# tia1.net
KiCad netlist of a schematic drawn in Altium Designer
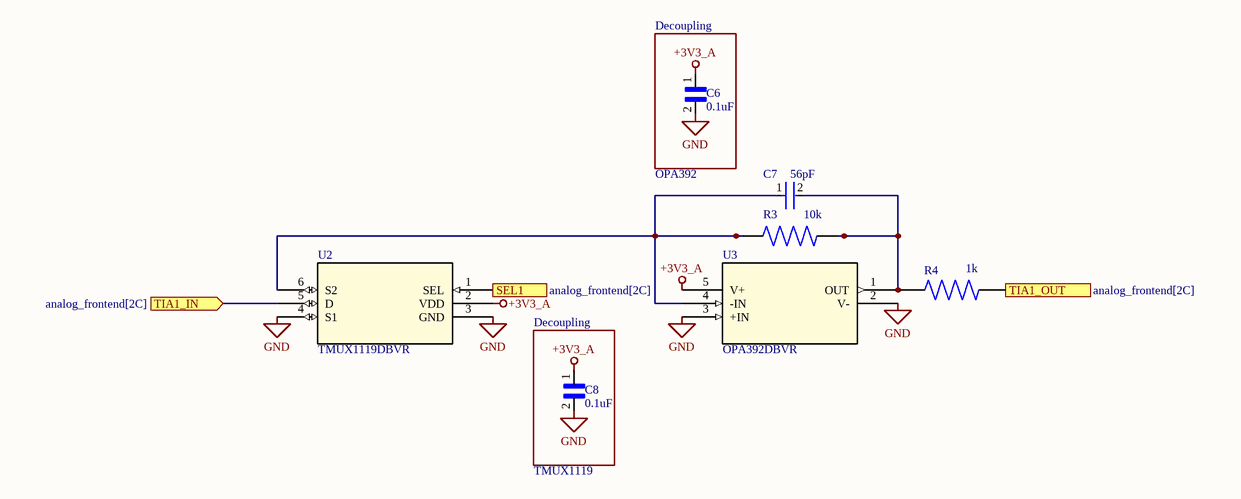
[diagram p0: tia1.SchDoc]

(export (version "E")
  (design (tool "Eeschema 10.0.6"))
  (components
    (comp (ref "C6")
      (value "0.1uF")
      (footprint "CC0603JRX7R8BB104")
      (description "25V 100nF X7R ±5% 0603 Multilayer Ceramic Capacitors MLCC - SMD/SMT ROHS")
      (fields
        (field (name "MANUFACTURER") "Yageo Group")
        (field (name "MANUFACTURER PART NUMBER") "CC0603JRX7R8BB104")
      )
      (libsource (lib "opm_lib") (part "CC0603JRX7R8BB104"))
    )
    (comp (ref "C7")
      (value "56pF")
      (footprint "GCM1885C2A560JA16D")
      (description "100V 56pF C0G ±5% 0603 Multilayer Ceramic Capacitors MLCC - SMD/SMT ROHS")
      (fields
        (field (name "MANUFACTURER") "Murata")
        (field (name "MANUFACTURER PART NUMBER") "GCM1885C2A560JA16D")
      )
      (libsource (lib "opm_lib") (part "GCM1885C2A560JA16D"))
    )
    (comp (ref "C8")
      (value "0.1uF")
      (footprint "CC0603JRX7R8BB104")
      (description "25V 100nF X7R ±5% 0603 Multilayer Ceramic Capacitors MLCC - SMD/SMT ROHS")
      (fields
        (field (name "MANUFACTURER") "Yageo Group")
        (field (name "MANUFACTURER PART NUMBER") "CC0603JRX7R8BB104")
      )
      (libsource (lib "opm_lib") (part "CC0603JRX7R8BB104"))
    )
    (comp (ref "R3")
      (value "10k")
      (footprint "RESC2012X55N")
      (description "Fixed Resistor, Thin Film, 0.125W, 10000ohm, 150V, 0.1% +/-Tol, 15ppm/Cel, Surface Mount, 0805")
      (fields
        (field (name "MANUFACTURER") "Vishay")
        (field (name "MANUFACTURER PART NUMBER") "TNPW080510K0BXEN")
      )
      (libsource (lib "opm_lib") (part "TNPW080510K0BXEN"))
    )
    (comp (ref "R4")
      (value "1k")
      (footprint "RESC1508X55N")
      (description "Fixed Resistor, Thin Film, 0.1W, 1000ohm, 75V, 0.1% +/-Tol, 15ppm/Cel, Surface Mount, 0603")
      (fields
        (field (name "MANUFACTURER") "Vishay")
        (field (name "MANUFACTURER PART NUMBER") "TNPW06031K00BXEN")
      )
      (libsource (lib "opm_lib") (part "TNPW06031K00BXEN"))
    )
    (comp (ref "U2")
      (value "TMUX1119DBVR")
      (footprint "TMUX1119DBVR")
      (fields (field (name "MANUFACTURER") "Texas Instruments"))
      (libsource (lib "opm_lib") (part "TMUX1119DBVR"))
    )
    (comp (ref "U3")
      (value "OPA392DBVR")
      (footprint "OPA392DBVR")
      (description "Operational Amplifier, 1 Func, 10uV Offset-Max, CMOS, PDSO5")
      (fields (field (name "MANUFACTURER") "Texas Instruments"))
      (libsource (lib "opm_lib") (part "OPA392DBVR"))
    )
  )
  (nets
    (net (code "1") (name "+3V3_A") (class "Default")
      (node (ref "C6") (pin "1") (pinfunction "1_1") (pintype "passive"))
      (node (ref "C8") (pin "1") (pinfunction "1_1") (pintype "passive"))
      (node (ref "U2") (pin "2") (pinfunction "VDD_2") (pintype "power_in"))
      (node (ref "U3") (pin "5") (pinfunction "V+_5") (pintype "power_in"))
    )
    (net (code "2") (name "/SEL1") (class "Default")
      (node (ref "U2") (pin "1") (pinfunction "SEL_1") (pintype "input"))
    )
    (net (code "3") (name "/TIA1_IN") (class "Default")
      (node (ref "U2") (pin "5") (pinfunction "D_5") (pintype "bidirectional"))
    )
    (net (code "4") (name "/TIA1_OUT") (class "Default")
      (node (ref "R4") (pin "2") (pinfunction "2_2") (pintype "passive"))
    )
    (net (code "5") (name "GND") (class "Default")
      (node (ref "C6") (pin "2") (pinfunction "2_2") (pintype "passive"))
      (node (ref "C8") (pin "2") (pinfunction "2_2") (pintype "passive"))
      (node (ref "U2") (pin "3") (pinfunction "GND_3") (pintype "power_in"))
      (node (ref "U2") (pin "4") (pinfunction "S1_4") (pintype "bidirectional"))
      (node (ref "U3") (pin "2") (pinfunction "V-_2") (pintype "power_in"))
      (node (ref "U3") (pin "3") (pinfunction "+IN_3") (pintype "input"))
    )
    (net (code "6") (name "Net-(U2-S2)") (class "Default")
      (node (ref "C7") (pin "1") (pinfunction "1_1") (pintype "passive"))
      (node (ref "R3") (pin "1") (pinfunction "1_1") (pintype "passive"))
      (node (ref "U2") (pin "6") (pinfunction "S2_6") (pintype "bidirectional"))
      (node (ref "U3") (pin "4") (pinfunction "-IN_4") (pintype "input"))
    )
    (net (code "7") (name "Net-(U3-OUT)") (class "Default")
      (node (ref "C7") (pin "2") (pinfunction "2_2") (pintype "passive"))
      (node (ref "R3") (pin "2") (pinfunction "2_2") (pintype "passive"))
      (node (ref "R4") (pin "1") (pinfunction "1_1") (pintype "passive"))
      (node (ref "U3") (pin "1") (pinfunction "OUT_1") (pintype "output"))
    )
  )
)
